# Display.net
KiCad netlist of a schematic drawn in Altium Designer
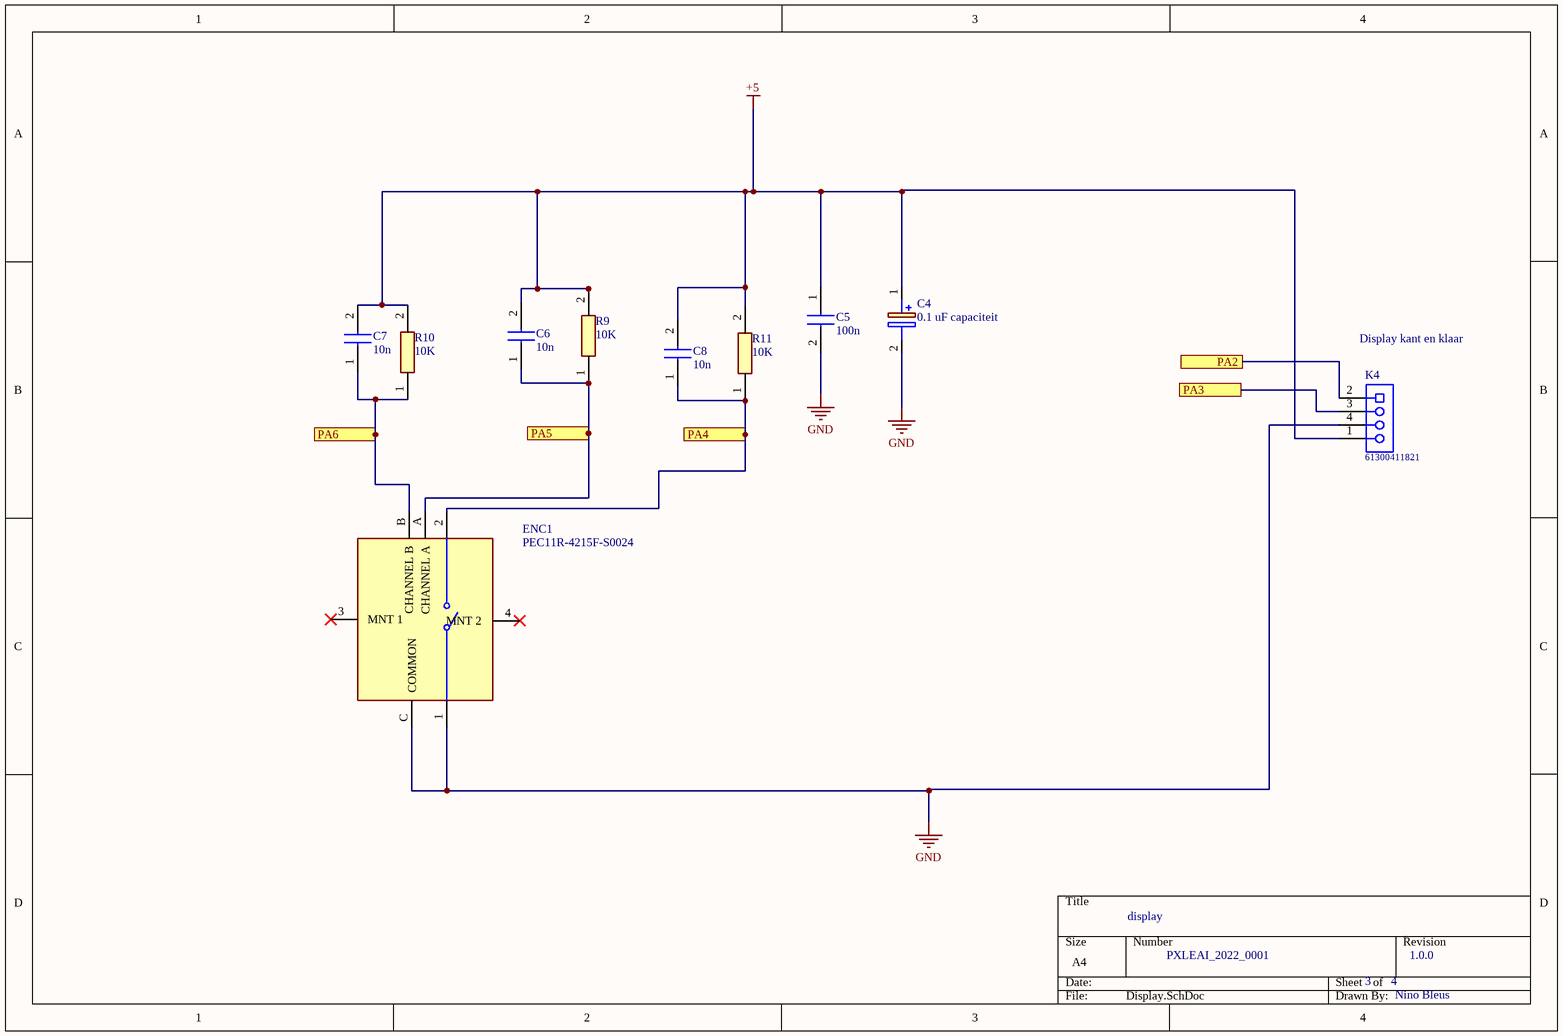
[diagram p0: Display.SchDoc]

(export (version "E")
  (design (tool "Eeschema 10.0.6"))
  (components
    (comp (ref "C4")
      (value "0.1 uF capaciteit")
      (footprint "SamacSys:CAPPRD200W52D500H1250")
      (description "Capacitor Polarised")
      (fields (field (name "MANUFACTURER_PART_NUMBER") "860010672001"))
      (libsource (lib "Schlib_soldeerbout") (part "0.1 uF capaciteit"))
    )
    (comp (ref "C5")
      (value "100n")
      (footprint "SamacSys:CAPC2012X88N")
      (description "Capacitor")
      (fields (field (name "MANUFACTURER_PART_NUMBER") "C0805C103K5RACTU"))
      (libsource (lib "Schlib_soldeerbout") (part "C0805C103K5RACTU"))
    )
    (comp (ref "C6")
      (value "10n")
      (footprint "SamacSys:CAPC2012X88N")
      (description "Capacitor")
      (fields (field (name "MANUFACTURER_PART_NUMBER") "C0805C103K5RACTU"))
      (libsource (lib "Schlib_soldeerbout") (part "C0805C103K5RACTU"))
    )
    (comp (ref "C7")
      (value "10n")
      (footprint "SamacSys:CAPC2012X88N")
      (description "Capacitor")
      (fields (field (name "MANUFACTURER_PART_NUMBER") "C0805C103K5RACTU"))
      (libsource (lib "Schlib_soldeerbout") (part "C0805C103K5RACTU"))
    )
    (comp (ref "C8")
      (value "10n")
      (footprint "SamacSys:CAPC2012X88N")
      (description "Capacitor")
      (fields (field (name "MANUFACTURER_PART_NUMBER") "C0805C103K5RACTU"))
      (libsource (lib "Schlib_soldeerbout") (part "C0805C103K5RACTU"))
    )
    (comp (ref "ENC1")
      (value "PEC11R-4215F-S0024")
      (footprint "FP-PEC11R-4215F-S0024-MFG")
      (description "ROTARY ENCODER MECHANICAL 24PPR")
      (libsource (lib "Schlib_soldeerbout") (part "CMP-1747-00012-2"))
    )
    (comp (ref "K4")
      (value "61300411821")
      (footprint "61300411821")
      (description "WR-PHD Socket Header, THT, pitch 2.54mm, Single Row, Vertical, 4p")
      (fields (field (name "MANUFACTURER") "Wurth Elektronik"))
      (libsource (lib "WR-PHD_Socket Header") (part "61300411821"))
    )
    (comp (ref "R9")
      (value "10K")
      (footprint "SamacSys:RESC2012X65N")
      (description "Resistor")
      (fields (field (name "MANUFACTURER_PART_NUMBER") "ESR10EZPJ183"))
      (libsource (lib "Schlib_soldeerbout") (part "ESR10EZPJ183"))
    )
    (comp (ref "R10")
      (value "10K")
      (footprint "SamacSys:RESC2012X65N")
      (description "Resistor")
      (fields (field (name "MANUFACTURER_PART_NUMBER") "ESR10EZPJ183"))
      (libsource (lib "Schlib_soldeerbout") (part "ESR10EZPJ183"))
    )
    (comp (ref "R11")
      (value "10K")
      (footprint "SamacSys:RESC2012X65N")
      (description "Resistor")
      (fields (field (name "MANUFACTURER_PART_NUMBER") "ESR10EZPJ183"))
      (libsource (lib "Schlib_soldeerbout") (part "ESR10EZPJ183"))
    )
  )
  (nets
    (net (code "1") (name "+5") (class "Default")
      (node (ref "C4") (pin "1") (pinfunction "+_1") (pintype "passive"))
      (node (ref "C5") (pin "1") (pinfunction "1_1") (pintype "passive"))
      (node (ref "C6") (pin "2") (pinfunction "2_2") (pintype "passive"))
      (node (ref "C7") (pin "2") (pinfunction "2_2") (pintype "passive"))
      (node (ref "C8") (pin "2") (pinfunction "2_2") (pintype "passive"))
      (node (ref "K4") (pin "1") (pinfunction "1_1") (pintype "passive"))
      (node (ref "R10") (pin "2") (pinfunction "2_2") (pintype "passive"))
      (node (ref "R11") (pin "2") (pinfunction "2_2") (pintype "passive"))
      (node (ref "R9") (pin "2") (pinfunction "2_2") (pintype "passive"))
    )
    (net (code "2") (name "/PA2") (class "Default")
      (node (ref "K4") (pin "2") (pinfunction "2_2") (pintype "passive"))
    )
    (net (code "3") (name "/PA3") (class "Default")
      (node (ref "K4") (pin "3") (pinfunction "3_3") (pintype "passive"))
    )
    (net (code "4") (name "/PA4") (class "Default")
      (node (ref "C8") (pin "1") (pinfunction "1_1") (pintype "passive"))
      (node (ref "ENC1") (pin "2") (pinfunction "2_2") (pintype "passive"))
      (node (ref "R11") (pin "1") (pinfunction "1_1") (pintype "passive"))
    )
    (net (code "5") (name "/PA5") (class "Default")
      (node (ref "C6") (pin "1") (pinfunction "1_1") (pintype "passive"))
      (node (ref "ENC1") (pin "A") (pinfunction "CHANNEL_A_A") (pintype "passive"))
      (node (ref "R9") (pin "1") (pinfunction "1_1") (pintype "passive"))
    )
    (net (code "6") (name "/PA6") (class "Default")
      (node (ref "C7") (pin "1") (pinfunction "1_1") (pintype "passive"))
      (node (ref "ENC1") (pin "B") (pinfunction "CHANNEL_B_B") (pintype "passive"))
      (node (ref "R10") (pin "1") (pinfunction "1_1") (pintype "passive"))
    )
    (net (code "7") (name "GND") (class "Default")
      (node (ref "C4") (pin "2") (pinfunction "-_2") (pintype "passive"))
      (node (ref "C5") (pin "2") (pinfunction "2_2") (pintype "passive"))
      (node (ref "ENC1") (pin "1") (pinfunction "1_1") (pintype "passive"))
      (node (ref "ENC1") (pin "C") (pinfunction "COMMON_C") (pintype "passive"))
      (node (ref "K4") (pin "4") (pinfunction "4_4") (pintype "passive"))
    )
    (net (code "8") (name "unconnected-(ENC1-MNT_1-Pad3)") (class "Default")
      (node (ref "ENC1") (pin "3") (pinfunction "MNT_1_3") (pintype "passive+no_connect"))
    )
    (net (code "9") (name "unconnected-(ENC1-MNT_2-Pad4)") (class "Default")
      (node (ref "ENC1") (pin "4") (pinfunction "MNT_2_4") (pintype "passive+no_connect"))
    )
  )
)
